# diakoptis_ver5.net
KiCad netlist of a schematic drawn in EAGLE
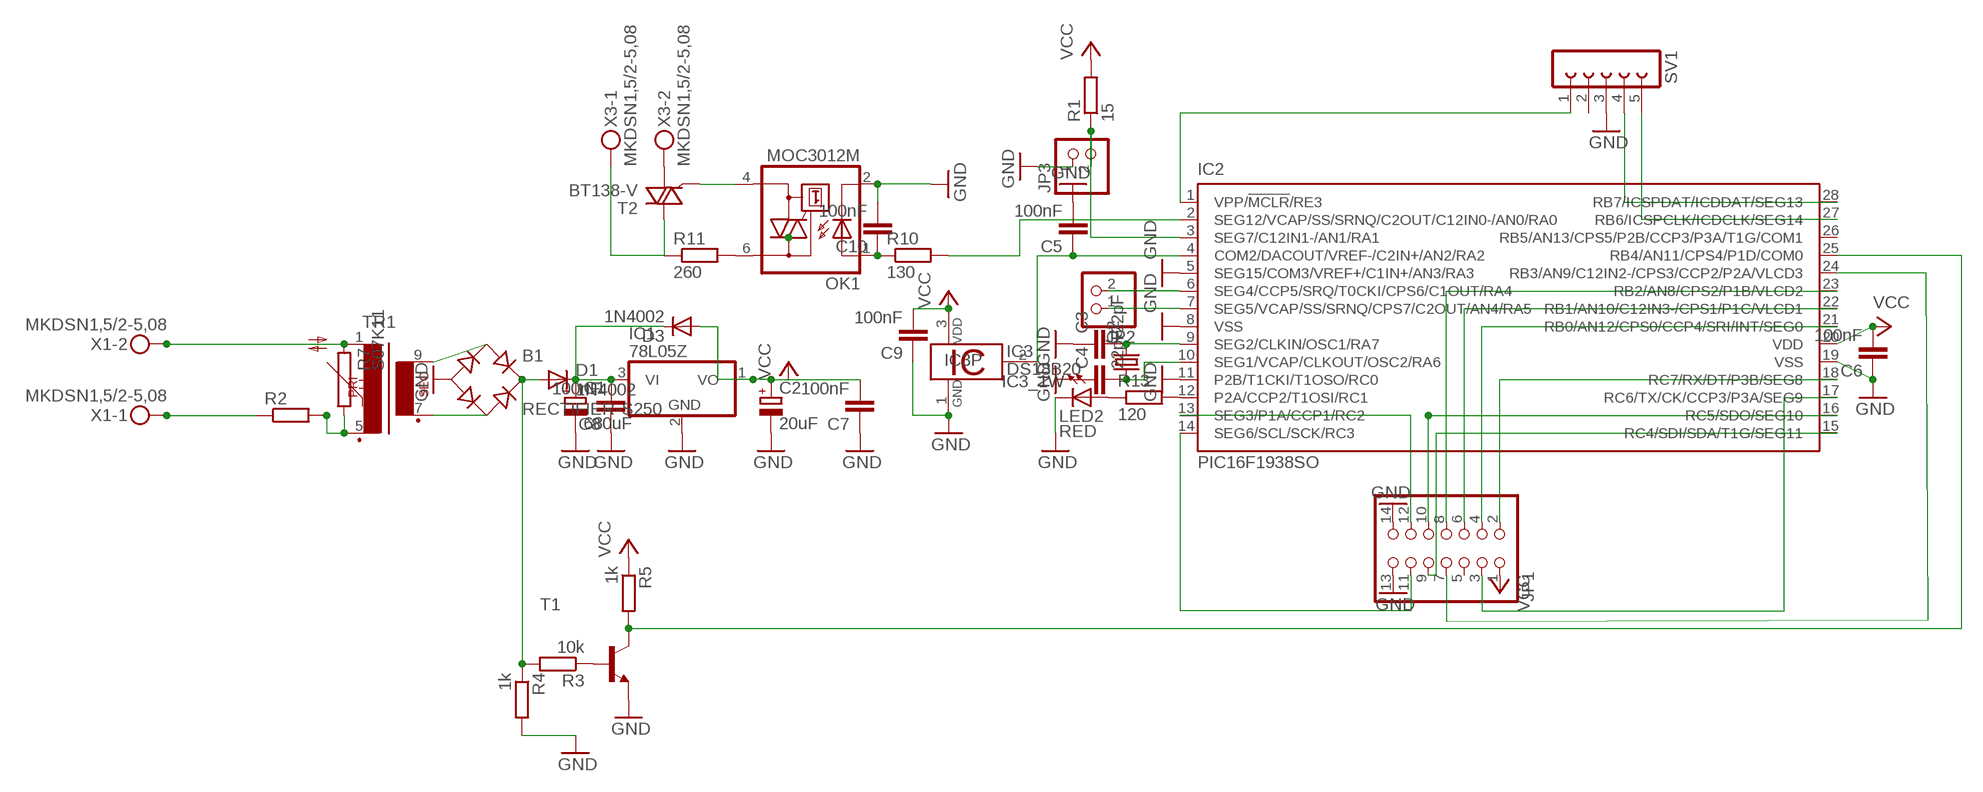
[diagram p0: schematic, sheet 1]

(export (version "E")
  (design (tool "Eeschema 10.0.6"))
  (components
    (comp (ref "B1")
      (value "RECTIFIER-S250")
      (footprint "eagle-import:TO-269AA")
      (libsource (lib "eagle-import") (part "RECTIFIER-S250"))
    )
    (comp (ref "C1")
      (value "680uF")
      (footprint "eagle-import:E3,5-10")
      (libsource (lib "eagle-import") (part "CPOL-EUE3.5-10"))
    )
    (comp (ref "C2")
      (value "20uF")
      (footprint "eagle-import:E1,8-4")
      (libsource (lib "eagle-import") (part "resistor_CPOL-EUE1.8-4"))
    )
    (comp (ref "C3")
      (value "22pF")
      (footprint "eagle-import:C1206")
      (libsource (lib "eagle-import") (part "C-EUC1206"))
    )
    (comp (ref "C4")
      (value "22pF")
      (footprint "eagle-import:C1206")
      (libsource (lib "eagle-import") (part "C-EUC1206"))
    )
    (comp (ref "C5")
      (value "100nF")
      (footprint "eagle-import:C0805")
      (libsource (lib "eagle-import") (part "C-EUC0805"))
    )
    (comp (ref "C6")
      (value "100nF")
      (footprint "eagle-import:C2.5-2")
      (libsource (lib "eagle-import") (part "C2.5/2"))
    )
    (comp (ref "C7")
      (value "100nF")
      (footprint "eagle-import:C1206K")
      (libsource (lib "eagle-import") (part "C-EUC1206K"))
    )
    (comp (ref "C8")
      (value "100nF")
      (footprint "eagle-import:C1206K")
      (libsource (lib "eagle-import") (part "C-EUC1206K"))
    )
    (comp (ref "C9")
      (value "100nF")
      (footprint "eagle-import:C1206")
      (libsource (lib "eagle-import") (part "C-EUC1206"))
    )
    (comp (ref "C10")
      (value "100nF")
      (footprint "eagle-import:C1206K")
      (libsource (lib "eagle-import") (part "C-EUC1206K"))
    )
    (comp (ref "D1")
      (value "1N4002")
      (footprint "eagle-import:D-5")
      (libsource (lib "eagle-import") (part "DIODE-D-5"))
    )
    (comp (ref "D3")
      (value "1N4002")
      (footprint "eagle-import:D-5")
      (libsource (lib "eagle-import") (part "DIODE-D-5"))
    )
    (comp (ref "IC1")
      (value "78L05Z")
      (footprint "eagle-import:TO92")
      (libsource (lib "eagle-import") (part "78ZL05"))
    )
    (comp (ref "IC2")
      (value "PIC16F1938SO")
      (footprint "eagle-import:SO28W")
      (fields
        (field (name "MPN") "PIC16F1938-I/SO")
        (field (name "MPN_1") "PIC16F1938-I/SO")
        (field (name "OC_FARNELL") "1755828")
        (field (name "OC_NEWARK") "08R1948")
      )
      (libsource (lib "eagle-import") (part "PIC16F19SO38"))
    )
    (comp (ref "IC3")
      (value "DS18B20")
      (footprint "eagle-import:TO92-")
      (libsource (lib "eagle-import") (part "DS18B20"))
    )
    (comp (ref "JP1")
      (value "PINHD-2X7")
      (footprint "eagle-import:2X07")
      (libsource (lib "eagle-import") (part "PINHD-2X7"))
    )
    (comp (ref "JP2")
      (value "PINHD-1X2")
      (footprint "eagle-import:1X02")
      (libsource (lib "eagle-import") (part "PINHD-1X2"))
    )
    (comp (ref "JP3")
      (value "PINHD-1X2")
      (footprint "eagle-import:1X02")
      (libsource (lib "eagle-import") (part "PINHD-1X2"))
    )
    (comp (ref "LED2")
      (value "RED")
      (footprint "eagle-import:LED3MM")
      (libsource (lib "eagle-import") (part "LED3MM"))
    )
    (comp (ref "OK1")
      (value "MOC3012M")
      (footprint "eagle-import:DIL06")
      (fields (field (name "MF") "FAIRCHILD SEMICONDUCTOR") (field (name "MPN") "MOC3012-M"))
      (libsource (lib "eagle-import") (part "MOC30M12"))
    )
    (comp (ref "Q2")
      (value "CRYSTALHC49U70")
      (footprint "eagle-import:HC49U70")
      (libsource (lib "eagle-import") (part "CRYSTALHC49U70"))
    )
    (comp (ref "R1")
      (value "15")
      (footprint "eagle-import:M1206")
      (libsource (lib "eagle-import") (part "R-EU_M1206"))
    )
    (comp (ref "R2")
      (value "R-EU_0204/5")
      (footprint "eagle-import:0204_5")
      (libsource (lib "eagle-import") (part "R-EU_0204/5"))
    )
    (comp (ref "R3")
      (value "10k")
      (footprint "eagle-import:M1206")
      (libsource (lib "eagle-import") (part "R-EU_M1206"))
    )
    (comp (ref "R4")
      (value "1k")
      (footprint "eagle-import:M1206")
      (libsource (lib "eagle-import") (part "R-EU_M1206"))
    )
    (comp (ref "R5")
      (value "1k")
      (footprint "eagle-import:M1206")
      (libsource (lib "eagle-import") (part "R-EU_M1206"))
    )
    (comp (ref "R7")
      (value "S07K11")
      (footprint "eagle-import:S07K11")
      (libsource (lib "eagle-import") (part "S07K11"))
    )
    (comp (ref "R10")
      (value "130")
      (footprint "eagle-import:M1206")
      (libsource (lib "eagle-import") (part "R-EU_M1206"))
    )
    (comp (ref "R11")
      (value "260")
      (footprint "eagle-import:M1206")
      (libsource (lib "eagle-import") (part "R-EU_M1206"))
    )
    (comp (ref "R13")
      (value "120")
      (footprint "eagle-import:M1206")
      (libsource (lib "eagle-import") (part "R-EU_M1206"))
    )
    (comp (ref "SV1")
      (value "FE05-1")
      (footprint "eagle-import:FE05-1")
      (libsource (lib "eagle-import") (part "FE05-1"))
    )
    (comp (ref "T1")
      (value "BC549-NPN-TO92-CBE")
      (footprint "eagle-import:TO92-CBE")
      (libsource (lib "eagle-import") (part "-NPN-TO92-CBEBC549"))
    )
    (comp (ref "T2")
      (value "BT138-V")
      (footprint "eagle-import:TO220BV")
      (libsource (lib "eagle-import") (part "BT138-V"))
    )
    (comp (ref "TR1")
      (value "VR11MINI")
      (footprint "eagle-import:VR11MINI")
      (libsource (lib "eagle-import") (part "VR11MINI"))
    )
    (comp (ref "X1")
      (value "MKDSN1,5/2-5,08")
      (footprint "eagle-import:MKDSN1,5_2-5,08")
      (fields (field (name "MPN") "MKDSN 1,5/2-5.08"))
      (libsource (lib "eagle-import") (part "MKDSN1,5/2-5,08"))
    )
    (comp (ref "X3")
      (value "MKDSN1,5/2-5,08")
      (footprint "eagle-import:MKDSN1,5_2-5,08")
      (fields (field (name "MPN") "MKDSN 1,5/2-5.08"))
      (libsource (lib "eagle-import") (part "MKDSN1,5/2-5,08"))
    )
  )
  (nets
    (net (code "1") (name "GND") (class "Default")
      (node (ref "B1") (pin "-") (pinfunction "-_-") (pintype "passive"))
      (node (ref "C1") (pin "-") (pinfunction "-_-") (pintype "passive"))
      (node (ref "C10") (pin "2") (pinfunction "2_2") (pintype "passive"))
      (node (ref "C2") (pin "-") (pinfunction "-_-") (pintype "passive"))
      (node (ref "C3") (pin "1") (pinfunction "1_1") (pintype "passive"))
      (node (ref "C4") (pin "1") (pinfunction "1_1") (pintype "passive"))
      (node (ref "C5") (pin "2") (pinfunction "2_2") (pintype "passive"))
      (node (ref "C6") (pin "1") (pinfunction "1_1") (pintype "passive"))
      (node (ref "C7") (pin "1") (pinfunction "1_1") (pintype "passive"))
      (node (ref "C8") (pin "1") (pinfunction "1_1") (pintype "passive"))
      (node (ref "C9") (pin "1") (pinfunction "1_1") (pintype "passive"))
      (node (ref "IC1") (pin "2") (pinfunction "GND_2") (pintype "passive"))
      (node (ref "IC2") (pin "11") (pinfunction "P2B/T1CKI/T1OSO/RC0_11") (pintype "bidirectional"))
      (node (ref "IC2") (pin "19") (pinfunction "VSS_19") (pintype "power_in"))
      (node (ref "IC2") (pin "5") (pinfunction "SEG15/COM3/VREF+/C1IN+/AN3/RA3_5") (pintype "bidirectional"))
      (node (ref "IC2") (pin "8") (pinfunction "VSS_8") (pintype "power_in"))
      (node (ref "IC3") (pin "1") (pinfunction "GND_1") (pintype "power_in"))
      (node (ref "JP1") (pin "13") (pinfunction "13_13") (pintype "passive"))
      (node (ref "JP1") (pin "14") (pinfunction "14_14") (pintype "passive"))
      (node (ref "JP3") (pin "1") (pinfunction "1_1") (pintype "passive"))
      (node (ref "LED2") (pin "K") (pinfunction "C_K") (pintype "passive"))
      (node (ref "OK1") (pin "2") (pinfunction "C_2") (pintype "passive"))
      (node (ref "R4") (pin "2") (pinfunction "2_2") (pintype "passive"))
      (node (ref "SV1") (pin "3") (pinfunction "3_3") (pintype "passive"))
      (node (ref "T1") (pin "E") (pinfunction "E_E") (pintype "passive"))
    )
    (net (code "2") (name "Net-(B1-Pad+)") (class "Default")
      (node (ref "B1") (pin "+") (pinfunction "+_+") (pintype "passive"))
      (node (ref "D1") (pin "A") (pinfunction "A_A") (pintype "passive"))
      (node (ref "R3") (pin "2") (pinfunction "2_2") (pintype "passive"))
      (node (ref "R4") (pin "1") (pinfunction "1_1") (pintype "passive"))
    )
    (net (code "3") (name "Net-(IC1-VI)") (class "Default")
      (node (ref "C1") (pin "+") (pinfunction "+_+") (pintype "passive"))
      (node (ref "C8") (pin "2") (pinfunction "2_2") (pintype "passive"))
      (node (ref "D1") (pin "C") (pinfunction "C_C") (pintype "passive"))
      (node (ref "D3") (pin "C") (pinfunction "C_C") (pintype "passive"))
      (node (ref "IC1") (pin "3") (pinfunction "VI_3") (pintype "input"))
    )
    (net (code "4") (name "Net-(IC2-COM2{slash}DACOUT{slash}VREF-{slash}C2IN+{slash}AN2{slash}RA2)") (class "Default")
      (node (ref "C5") (pin "1") (pinfunction "1_1") (pintype "passive"))
      (node (ref "IC2") (pin "4") (pinfunction "COM2/DACOUT/VREF-/C2IN+/AN2/RA2_4") (pintype "bidirectional"))
      (node (ref "IC3") (pin "2") (pinfunction "1W_2") (pintype "power_in"))
    )
    (net (code "5") (name "Net-(IC2-P2A{slash}CCP2{slash}T1OSI{slash}RC1)") (class "Default")
      (node (ref "IC2") (pin "12") (pinfunction "P2A/CCP2/T1OSI/RC1_12") (pintype "bidirectional"))
      (node (ref "R13") (pin "2") (pinfunction "2_2") (pintype "passive"))
    )
    (net (code "6") (name "Net-(IC2-RB0{slash}AN12{slash}CPS0{slash}CCP4{slash}SRI{slash}INT{slash}SEG0)") (class "Default")
      (node (ref "IC2") (pin "21") (pinfunction "RB0/AN12/CPS0/CCP4/SRI/INT/SEG0_21") (pintype "bidirectional"))
      (node (ref "JP1") (pin "4") (pinfunction "4_4") (pintype "passive"))
    )
    (net (code "7") (name "Net-(IC2-RB1{slash}AN10{slash}C12IN3-{slash}CPS1{slash}P1C{slash}VLCD1)") (class "Default")
      (node (ref "IC2") (pin "22") (pinfunction "RB1/AN10/C12IN3-/CPS1/P1C/VLCD1_22") (pintype "bidirectional"))
      (node (ref "JP1") (pin "6") (pinfunction "6_6") (pintype "passive"))
    )
    (net (code "8") (name "Net-(IC2-RB2{slash}AN8{slash}CPS2{slash}P1B{slash}VLCD2)") (class "Default")
      (node (ref "IC2") (pin "23") (pinfunction "RB2/AN8/CPS2/P1B/VLCD2_23") (pintype "bidirectional"))
      (node (ref "JP1") (pin "8") (pinfunction "8_8") (pintype "passive"))
    )
    (net (code "9") (name "Net-(IC2-RB3{slash}AN9{slash}C12IN2-{slash}CPS3{slash}CCP2{slash}P2A{slash}VLCD3)") (class "Default")
      (node (ref "IC2") (pin "24") (pinfunction "RB3/AN9/C12IN2-/CPS3/CCP2/P2A/VLCD3_24") (pintype "bidirectional"))
      (node (ref "JP1") (pin "7") (pinfunction "7_7") (pintype "passive"))
    )
    (net (code "10") (name "Net-(IC2-RB4{slash}AN11{slash}CPS4{slash}P1D{slash}COM0)") (class "Default")
      (node (ref "IC2") (pin "25") (pinfunction "RB4/AN11/CPS4/P1D/COM0_25") (pintype "bidirectional"))
      (node (ref "R5") (pin "2") (pinfunction "2_2") (pintype "passive"))
      (node (ref "T1") (pin "C") (pinfunction "C_C") (pintype "passive"))
    )
    (net (code "11") (name "Net-(IC2-RB6{slash}ICSPCLK{slash}ICDCLK{slash}SEG14)") (class "Default")
      (node (ref "IC2") (pin "27") (pinfunction "RB6/ICSPCLK/ICDCLK/SEG14_27") (pintype "bidirectional"))
      (node (ref "SV1") (pin "5") (pinfunction "5_5") (pintype "passive"))
    )
    (net (code "12") (name "Net-(IC2-RB7{slash}ICSPDAT{slash}ICDDAT{slash}SEG13)") (class "Default")
      (node (ref "IC2") (pin "28") (pinfunction "RB7/ICSPDAT/ICDDAT/SEG13_28") (pintype "bidirectional"))
      (node (ref "SV1") (pin "4") (pinfunction "4_4") (pintype "passive"))
    )
    (net (code "13") (name "Net-(IC2-RC4{slash}SDI{slash}SDA{slash}T1G{slash}SEG11)") (class "Default")
      (node (ref "IC2") (pin "15") (pinfunction "RC4/SDI/SDA/T1G/SEG11_15") (pintype "bidirectional"))
      (node (ref "JP1") (pin "9") (pinfunction "9_9") (pintype "passive"))
    )
    (net (code "14") (name "Net-(IC2-RC5{slash}SDO{slash}SEG10)") (class "Default")
      (node (ref "IC2") (pin "16") (pinfunction "RC5/SDO/SEG10_16") (pintype "bidirectional"))
      (node (ref "JP1") (pin "10") (pinfunction "10_10") (pintype "passive"))
    )
    (net (code "15") (name "Net-(IC2-RC6{slash}TX{slash}CK{slash}CCP3{slash}P3A{slash}SEG9)") (class "Default")
      (node (ref "IC2") (pin "17") (pinfunction "RC6/TX/CK/CCP3/P3A/SEG9_17") (pintype "bidirectional"))
      (node (ref "JP1") (pin "3") (pinfunction "3_3") (pintype "passive"))
    )
    (net (code "16") (name "Net-(IC2-RC7{slash}RX{slash}DT{slash}P3B{slash}SEG8)") (class "Default")
      (node (ref "IC2") (pin "18") (pinfunction "RC7/RX/DT/P3B/SEG8_18") (pintype "bidirectional"))
      (node (ref "JP1") (pin "2") (pinfunction "2_2") (pintype "passive"))
    )
    (net (code "17") (name "Net-(IC2-SEG1{slash}VCAP{slash}CLKOUT{slash}OSC2{slash}RA6)") (class "Default")
      (node (ref "C4") (pin "2") (pinfunction "2_2") (pintype "passive"))
      (node (ref "IC2") (pin "10") (pinfunction "SEG1/VCAP/CLKOUT/OSC2/RA6_10") (pintype "bidirectional"))
      (node (ref "Q2") (pin "1") (pinfunction "1_1") (pintype "passive"))
    )
    (net (code "18") (name "Net-(IC2-SEG2{slash}CLKIN{slash}OSC1{slash}RA7)") (class "Default")
      (node (ref "C3") (pin "2") (pinfunction "2_2") (pintype "passive"))
      (node (ref "IC2") (pin "9") (pinfunction "SEG2/CLKIN/OSC1/RA7_9") (pintype "bidirectional"))
      (node (ref "Q2") (pin "2") (pinfunction "2_2") (pintype "passive"))
    )
    (net (code "19") (name "Net-(IC2-SEG3{slash}P1A{slash}CCP1{slash}RC2)") (class "Default")
      (node (ref "IC2") (pin "13") (pinfunction "SEG3/P1A/CCP1/RC2_13") (pintype "bidirectional"))
      (node (ref "JP1") (pin "12") (pinfunction "12_12") (pintype "passive"))
    )
    (net (code "20") (name "Net-(IC2-SEG4{slash}CCP5{slash}SRQ{slash}T0CKI{slash}CPS6{slash}C1OUT{slash}RA4)") (class "Default")
      (node (ref "IC2") (pin "6") (pinfunction "SEG4/CCP5/SRQ/T0CKI/CPS6/C1OUT/RA4_6") (pintype "bidirectional"))
      (node (ref "JP2") (pin "2") (pinfunction "2_2") (pintype "passive"))
    )
    (net (code "21") (name "Net-(IC2-SEG5{slash}VCAP{slash}SS{slash}SRNQ{slash}CPS7{slash}C2OUT{slash}AN4{slash}RA5)") (class "Default")
      (node (ref "IC2") (pin "7") (pinfunction "SEG5/VCAP/SS/SRNQ/CPS7/C2OUT/AN4/RA5_7") (pintype "bidirectional"))
      (node (ref "JP2") (pin "1") (pinfunction "1_1") (pintype "passive"))
    )
    (net (code "22") (name "Net-(IC2-SEG6{slash}SCL{slash}SCK{slash}RC3)") (class "Default")
      (node (ref "IC2") (pin "14") (pinfunction "SEG6/SCL/SCK/RC3_14") (pintype "bidirectional"))
      (node (ref "JP1") (pin "11") (pinfunction "11_11") (pintype "passive"))
    )
    (net (code "23") (name "Net-(IC2-SEG7{slash}C12IN1-{slash}AN1{slash}RA1)") (class "Default")
      (node (ref "IC2") (pin "3") (pinfunction "SEG7/C12IN1-/AN1/RA1_3") (pintype "bidirectional"))
      (node (ref "JP3") (pin "2") (pinfunction "2_2") (pintype "passive"))
      (node (ref "R1") (pin "1") (pinfunction "1_1") (pintype "passive"))
    )
    (net (code "24") (name "Net-(IC2-SEG12{slash}VCAP{slash}SS{slash}SRNQ{slash}C2OUT{slash}C12IN0-{slash}AN0{slash}RA0)") (class "Default")
      (node (ref "IC2") (pin "2") (pinfunction "SEG12/VCAP/SS/SRNQ/C2OUT/C12IN0-/AN0/RA0_2") (pintype "bidirectional"))
      (node (ref "R10") (pin "2") (pinfunction "2_2") (pintype "passive"))
    )
    (net (code "25") (name "Net-(IC2-VPP{slash}~{MCLR}{slash}RE3)") (class "Default")
      (node (ref "IC2") (pin "1") (pinfunction "VPP/~{MCLR}/RE3_1") (pintype "input"))
      (node (ref "SV1") (pin "1") (pinfunction "1_1") (pintype "passive"))
    )
    (net (code "26") (name "Net-(LED2-PadA)") (class "Default")
      (node (ref "LED2") (pin "A") (pinfunction "A_A") (pintype "passive"))
      (node (ref "R13") (pin "1") (pinfunction "1_1") (pintype "passive"))
    )
    (net (code "27") (name "Net-(OK1-A)") (class "Default")
      (node (ref "C10") (pin "1") (pinfunction "1_1") (pintype "passive"))
      (node (ref "OK1") (pin "1") (pinfunction "A_1") (pintype "passive"))
      (node (ref "R10") (pin "1") (pinfunction "1_1") (pintype "passive"))
    )
    (net (code "28") (name "Net-(OK1-A1)") (class "Default")
      (node (ref "OK1") (pin "4") (pinfunction "A1_4") (pintype "passive"))
      (node (ref "T2") (pin "G") (pinfunction "G_G") (pintype "passive"))
    )
    (net (code "29") (name "Net-(OK1-A2)") (class "Default")
      (node (ref "OK1") (pin "6") (pinfunction "A2_6") (pintype "passive"))
      (node (ref "R11") (pin "2") (pinfunction "2_2") (pintype "passive"))
    )
    (net (code "30") (name "Net-(R3-Pad1)") (class "Default")
      (node (ref "R3") (pin "1") (pinfunction "1_1") (pintype "passive"))
      (node (ref "T1") (pin "B") (pinfunction "B_B") (pintype "passive"))
    )
    (net (code "31") (name "Net-(T2-A1)") (class "Default")
      (node (ref "T2") (pin "T1") (pinfunction "A1_T1") (pintype "passive"))
      (node (ref "X3") (pin "2") (pinfunction "KL_2") (pintype "passive"))
    )
    (net (code "32") (name "Net-(T2-A2)") (class "Default")
      (node (ref "R11") (pin "1") (pinfunction "1_1") (pintype "passive"))
      (node (ref "T2") (pin "T2") (pinfunction "A2_T2") (pintype "passive"))
      (node (ref "X3") (pin "1") (pinfunction "KL_1") (pintype "passive"))
    )
    (net (code "33") (name "Net-(TR1-P1)") (class "Default")
      (node (ref "R7") (pin "2") (pinfunction "2_2") (pintype "passive"))
      (node (ref "TR1") (pin "1") (pinfunction "P1_1") (pintype "passive"))
      (node (ref "X1") (pin "2") (pinfunction "KL_2") (pintype "passive"))
    )
    (net (code "34") (name "Net-(TR1-P2)") (class "Default")
      (node (ref "R2") (pin "2") (pinfunction "2_2") (pintype "passive"))
      (node (ref "R7") (pin "1") (pinfunction "1_1") (pintype "passive"))
      (node (ref "TR1") (pin "5") (pinfunction "P2_5") (pintype "passive"))
    )
    (net (code "35") (name "Net-(TR1-S3)") (class "Default")
      (node (ref "B1") (pin "AC2") (pinfunction "AC2_AC2") (pintype "passive"))
      (node (ref "TR1") (pin "7") (pinfunction "S3_7") (pintype "passive"))
    )
    (net (code "36") (name "Net-(TR1-S4)") (class "Default")
      (node (ref "B1") (pin "AC1") (pinfunction "AC1_AC1") (pintype "passive"))
      (node (ref "TR1") (pin "9") (pinfunction "S4_9") (pintype "passive"))
    )
    (net (code "37") (name "Net-(X1A-KL)") (class "Default")
      (node (ref "R2") (pin "1") (pinfunction "1_1") (pintype "passive"))
      (node (ref "X1") (pin "1") (pinfunction "KL_1") (pintype "passive"))
    )
    (net (code "38") (name "VCC") (class "Default")
      (node (ref "C2") (pin "+") (pinfunction "+_+") (pintype "passive"))
      (node (ref "C6") (pin "2") (pinfunction "2_2") (pintype "passive"))
      (node (ref "C7") (pin "2") (pinfunction "2_2") (pintype "passive"))
      (node (ref "C9") (pin "2") (pinfunction "2_2") (pintype "passive"))
      (node (ref "D3") (pin "A") (pinfunction "A_A") (pintype "passive"))
      (node (ref "IC1") (pin "1") (pinfunction "VO_1") (pintype "passive"))
      (node (ref "IC2") (pin "20") (pinfunction "VDD_20") (pintype "power_in"))
      (node (ref "IC3") (pin "3") (pinfunction "VDD_3") (pintype "power_in"))
      (node (ref "JP1") (pin "1") (pinfunction "1_1") (pintype "passive"))
      (node (ref "R1") (pin "2") (pinfunction "2_2") (pintype "passive"))
      (node (ref "R5") (pin "1") (pinfunction "1_1") (pintype "passive"))
    )
    (net (code "39") (name "unconnected-(IC2-RB5{slash}AN13{slash}CPS5{slash}P2B{slash}CCP3{slash}P3A{slash}T1G{slash}COM1-Pad26)") (class "Default")
      (node (ref "IC2") (pin "26") (pinfunction "RB5/AN13/CPS5/P2B/CCP3/P3A/T1G/COM1_26") (pintype "bidirectional"))
    )
    (net (code "40") (name "unconnected-(JP1-Pad5)") (class "Default")
      (node (ref "JP1") (pin "5") (pinfunction "5_5") (pintype "passive"))
    )
    (net (code "41") (name "unconnected-(SV1-Pad2)") (class "Default")
      (node (ref "SV1") (pin "2") (pinfunction "2_2") (pintype "passive"))
    )
  )
)
